# Peripherals.net
KiCad netlist of a schematic drawn in Altium Designer
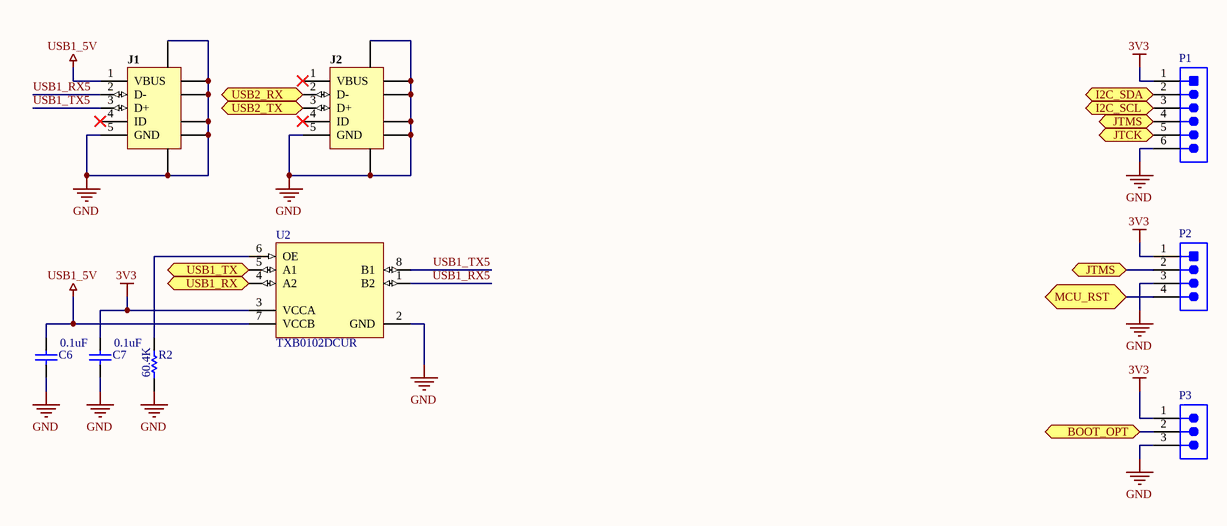
[diagram p0: Peripherals.SchDoc]

(export (version "E")
  (design (tool "Eeschema 10.0.6"))
  (components
    (comp (ref "C6")
      (value "0.1uF")
      (footprint "CAPC3216X100X50LL20T25")
      (description "CAP CER 0.1UF 25V 10% X7R 1206")
      (fields (field (name "PARTNUMBER") "C1206F104K3RACTU"))
      (libsource (lib "Altium Content Vault") (part "CAP-NP-2"))
    )
    (comp (ref "C7")
      (value "0.1uF")
      (footprint "CAPC3216X100X50LL20T25")
      (description "CAP CER 0.1UF 25V 10% X7R 1206")
      (fields (field (name "PARTNUMBER") "C1206F104K3RACTU"))
      (libsource (lib "Altium Content Vault") (part "CAP-NP-2"))
    )
    (comp (ref "J1")
      (value "ZX62R-B-5P")
      (footprint "HIRO-ZX62R-B-5P_V")
      (description "Connector; USBMicro-B,Reverse type, SMT; 5 Position; Right Angle")
      (libsource (lib "Altium Content Vault") (part "HIRO-ZX62R-B-5P-5"))
    )
    (comp (ref "J2")
      (value "ZX62R-B-5P")
      (footprint "HIRO-ZX62R-B-5P_V")
      (description "Connector; USBMicro-B,Reverse type, SMT; 5 Position; Right Angle")
      (libsource (lib "Altium Content Vault") (part "HIRO-ZX62R-B-5P-5"))
    )
    (comp (ref "P1")
      (value "22-23-2061")
      (footprint "MOLX-22-23-2061_V")
      (fields (field (name "MANUFACTURER") "Molex"))
      (libsource (lib "Altium Content Vault") (part "CN-1P-M-R6"))
    )
    (comp (ref "P2")
      (value "22-23-2041")
      (footprint "22-23-2041")
      (description "MOLEX 4POS MALE HEADER VERT")
      (libsource (lib "HRTAltiumLib") (part "22-23-2041"))
    )
    (comp (ref "P3")
      (value "PTT-103-01-L-S")
      (footprint "SMTC-PTT-103-01-X-S")
      (description "Press Fit Header, Through-hole, Vertical, -55 to 125 degC, 2 mm Pitch, 3-Pin, Male, RoHS")
      (fields (field (name "MANUFACTURER") "Samtec"))
      (libsource (lib "Altium Content Vault") (part "SMTC-PTT-103-01-X-S"))
    )
    (comp (ref "R2")
      (value "60.4K")
      (footprint "RESC1206(3216)_M")
      (description "60K4 0.25W 1% 1206 (3216 Metric)  SMD")
      (fields (field (name "TOLERANCE") "1 %") (field (name "POWER") "0.25 W"))
      (libsource (lib "Altium Content Vault") (part "RES"))
    )
    (comp (ref "U2")
      (value "TXB0102DCUR")
      (footprint "DCU0008A_N")
      (fields
        (field (name "MANUFACTURER") "Texas Instruments")
        (field (name "GENERIC PART NUMBER") "TXB0102")
      )
      (libsource (lib "Altium Content Vault") (part "TI-TXB0102-DCU0008A-8"))
    )
  )
  (nets
    (net (code "1") (name "/BOOT_OPT") (class "Default")
      (node (ref "P3") (pin "2") (pinfunction "2_2") (pintype "passive"))
    )
    (net (code "2") (name "/I2C_SCL") (class "Default")
      (node (ref "P1") (pin "3") (pinfunction "3_3") (pintype "passive"))
    )
    (net (code "3") (name "/I2C_SDA") (class "Default")
      (node (ref "P1") (pin "2") (pinfunction "2_2") (pintype "passive"))
    )
    (net (code "4") (name "/JTCK") (class "Default")
      (node (ref "P1") (pin "5") (pinfunction "5_5") (pintype "passive"))
    )
    (net (code "5") (name "/JTMS") (class "Default")
      (node (ref "P1") (pin "4") (pinfunction "4_4") (pintype "passive"))
      (node (ref "P2") (pin "2") (pinfunction "2_2") (pintype "passive"))
    )
    (net (code "6") (name "/MCU_RST") (class "Default")
      (node (ref "P2") (pin "4") (pinfunction "4_4") (pintype "passive"))
    )
    (net (code "7") (name "/USB1_RX") (class "Default")
      (node (ref "U2") (pin "4") (pinfunction "A2_4") (pintype "bidirectional"))
    )
    (net (code "8") (name "/USB1_RX5") (class "Default")
      (node (ref "J1") (pin "2") (pinfunction "D-_2") (pintype "bidirectional"))
      (node (ref "U2") (pin "1") (pinfunction "B2_1") (pintype "bidirectional"))
    )
    (net (code "9") (name "/USB1_TX") (class "Default")
      (node (ref "U2") (pin "5") (pinfunction "A1_5") (pintype "bidirectional"))
    )
    (net (code "10") (name "/USB1_TX5") (class "Default")
      (node (ref "J1") (pin "3") (pinfunction "D+_3") (pintype "bidirectional"))
      (node (ref "U2") (pin "8") (pinfunction "B1_8") (pintype "bidirectional"))
    )
    (net (code "11") (name "/USB2_RX") (class "Default")
      (node (ref "J2") (pin "2") (pinfunction "D-_2") (pintype "bidirectional"))
    )
    (net (code "12") (name "/USB2_TX") (class "Default")
      (node (ref "J2") (pin "3") (pinfunction "D+_3") (pintype "bidirectional"))
    )
    (net (code "13") (name "3V3") (class "Default")
      (node (ref "C7") (pin "1") (pinfunction "1_1") (pintype "passive"))
      (node (ref "P1") (pin "1") (pinfunction "1_1") (pintype "passive"))
      (node (ref "P2") (pin "1") (pinfunction "1_1") (pintype "passive"))
      (node (ref "P3") (pin "1") (pinfunction "1_1") (pintype "passive"))
      (node (ref "U2") (pin "3") (pinfunction "VCCA_3") (pintype "power_in"))
    )
    (net (code "14") (name "GND") (class "Default")
      (node (ref "C6") (pin "2") (pinfunction "2_2") (pintype "passive"))
      (node (ref "C7") (pin "2") (pinfunction "2_2") (pintype "passive"))
      (node (ref "J1") (pin "10") (pinfunction "SHLD_10") (pintype "passive"))
      (node (ref "J1") (pin "11") (pinfunction "SHLD_11") (pintype "passive"))
      (node (ref "J1") (pin "5") (pinfunction "GND_5") (pintype "power_in"))
      (node (ref "J1") (pin "6") (pinfunction "SHLD_6") (pintype "passive"))
      (node (ref "J1") (pin "7") (pinfunction "SHLD_7") (pintype "passive"))
      (node (ref "J1") (pin "8") (pinfunction "SHLD_8") (pintype "passive"))
      (node (ref "J1") (pin "9") (pinfunction "SHLD_9") (pintype "passive"))
      (node (ref "J2") (pin "10") (pinfunction "SHLD_10") (pintype "passive"))
      (node (ref "J2") (pin "11") (pinfunction "SHLD_11") (pintype "passive"))
      (node (ref "J2") (pin "5") (pinfunction "GND_5") (pintype "power_in"))
      (node (ref "J2") (pin "6") (pinfunction "SHLD_6") (pintype "passive"))
      (node (ref "J2") (pin "7") (pinfunction "SHLD_7") (pintype "passive"))
      (node (ref "J2") (pin "8") (pinfunction "SHLD_8") (pintype "passive"))
      (node (ref "J2") (pin "9") (pinfunction "SHLD_9") (pintype "passive"))
      (node (ref "P1") (pin "6") (pinfunction "6_6") (pintype "passive"))
      (node (ref "P2") (pin "3") (pinfunction "3_3") (pintype "passive"))
      (node (ref "P3") (pin "3") (pinfunction "3_3") (pintype "passive"))
      (node (ref "R2") (pin "1") (pinfunction "1_1") (pintype "passive"))
      (node (ref "U2") (pin "2") (pinfunction "GND_2") (pintype "power_in"))
    )
    (net (code "15") (name "Net-(U2-OE)") (class "Default")
      (node (ref "R2") (pin "2") (pinfunction "2_2") (pintype "passive"))
      (node (ref "U2") (pin "6") (pinfunction "OE_6") (pintype "input"))
    )
    (net (code "16") (name "USB1_5V") (class "Default")
      (node (ref "C6") (pin "1") (pinfunction "1_1") (pintype "passive"))
      (node (ref "J1") (pin "1") (pinfunction "VBUS_1") (pintype "power_in"))
      (node (ref "U2") (pin "7") (pinfunction "VCCB_7") (pintype "power_in"))
    )
    (net (code "17") (name "unconnected-(J1-ID-Pad4)") (class "Default")
      (node (ref "J1") (pin "4") (pinfunction "ID_4") (pintype "passive+no_connect"))
    )
    (net (code "18") (name "unconnected-(J2-ID-Pad4)") (class "Default")
      (node (ref "J2") (pin "4") (pinfunction "ID_4") (pintype "passive+no_connect"))
    )
    (net (code "19") (name "unconnected-(J2-VBUS-Pad1)") (class "Default")
      (node (ref "J2") (pin "1") (pinfunction "VBUS_1") (pintype "power_in+no_connect"))
    )
  )
)
